# main.net
KiCad netlist of a schematic drawn in Altium Designer
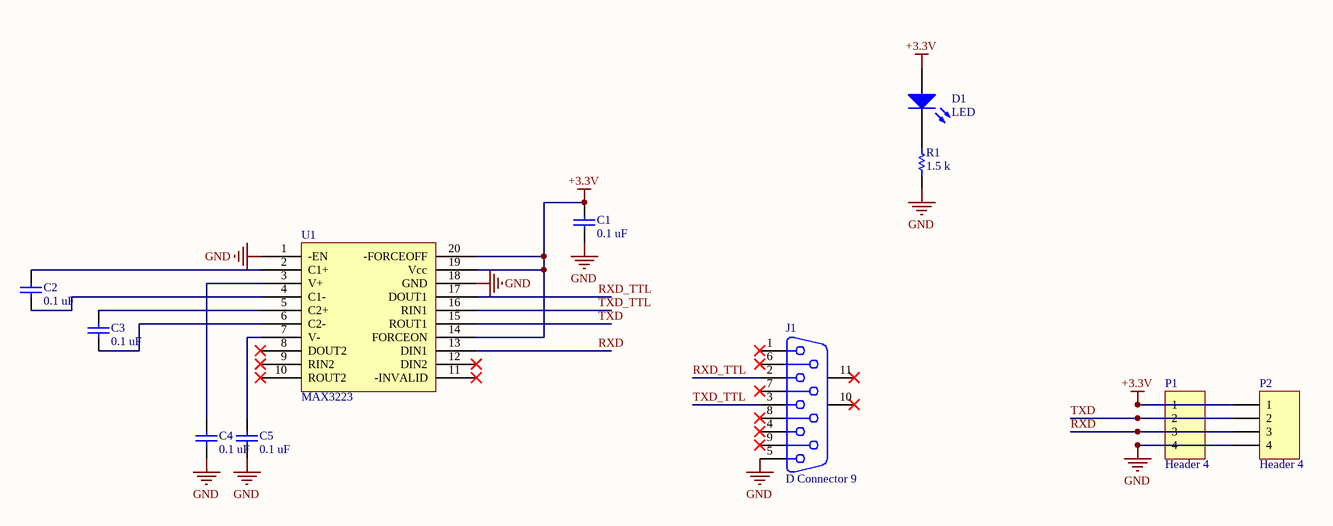
[diagram p0: main.SchDoc]

(export (version "E")
  (design (tool "Eeschema 10.0.6"))
  (components
    (comp (ref "C1")
      (value "0.1 uF")
      (footprint "0603")
      (description "Capacitor")
      (libsource (lib "allspace_schem") (part "Capacitor"))
    )
    (comp (ref "C2")
      (value "0.1 uF")
      (footprint "0603")
      (description "Capacitor")
      (libsource (lib "allspace_schem") (part "Capacitor"))
    )
    (comp (ref "C3")
      (value "0.1 uF")
      (footprint "0603")
      (description "Capacitor")
      (libsource (lib "allspace_schem") (part "Capacitor"))
    )
    (comp (ref "C4")
      (value "0.1 uF")
      (footprint "0603")
      (description "Capacitor")
      (libsource (lib "allspace_schem") (part "Capacitor"))
    )
    (comp (ref "C5")
      (value "0.1 uF")
      (footprint "0603")
      (description "Capacitor")
      (libsource (lib "allspace_schem") (part "Capacitor"))
    )
    (comp (ref "D1")
      (value "LED")
      (footprint "0603")
      (description "Typical INFRARED GaAs LED")
      (libsource (lib "allspace_schem") (part "LED"))
    )
    (comp (ref "J1")
      (value "D Connector 9")
      (footprint "DSUB1.385-2H9")
      (description "Receptacle Assembly, 9 Position, Right Angle")
      (fields (field (name "PUBLISHER") "Altium Limited"))
      (libsource (lib "Miscellaneous Connectors") (part "D Connector 9"))
    )
    (comp (ref "P1")
      (value "Header 4")
      (footprint "HDR1X4")
      (description "Header, 4-Pin")
      (fields (field (name "PUBLISHER") "Altium Limited"))
      (libsource (lib "allspace_schem") (part "Header 4"))
    )
    (comp (ref "P2")
      (value "Header 4")
      (footprint "MICRO-04-R-SMT")
      (description "Header, 4-Pin")
      (fields (field (name "PUBLISHER") "Altium Limited"))
      (libsource (lib "allspace_schem") (part "Header 4"))
    )
    (comp (ref "R1")
      (value "1.5 k")
      (footprint "0603")
      (description "Resistor")
      (libsource (lib "allspace_schem") (part "Resistor"))
    )
    (comp (ref "U1")
      (value "MAX3223")
      (footprint "TSSOP-20")
      (libsource (lib "allspace_schem") (part "MAX3223"))
    )
  )
  (nets
    (net (code "1") (name "+3.3V") (class "Default")
      (node (ref "C1") (pin "2") (pinfunction "2_2") (pintype "passive"))
      (node (ref "D1") (pin "1") (pinfunction "A_1") (pintype "passive"))
      (node (ref "P1") (pin "1") (pinfunction "1_1") (pintype "passive"))
      (node (ref "P2") (pin "1") (pinfunction "1_1") (pintype "passive"))
      (node (ref "U1") (pin "14") (pinfunction "FORCEON_14") (pintype "passive"))
      (node (ref "U1") (pin "19") (pinfunction "Vcc_19") (pintype "passive"))
      (node (ref "U1") (pin "20") (pinfunction "-FORCEOFF_20") (pintype "passive"))
    )
    (net (code "2") (name "/RXD") (class "Default")
      (node (ref "P1") (pin "3") (pinfunction "3_3") (pintype "passive"))
      (node (ref "P2") (pin "3") (pinfunction "3_3") (pintype "passive"))
      (node (ref "U1") (pin "13") (pinfunction "DIN1_13") (pintype "passive"))
    )
    (net (code "3") (name "/RXD_TTL") (class "Default")
      (node (ref "J1") (pin "2") (pinfunction "2_2") (pintype "passive"))
      (node (ref "U1") (pin "17") (pinfunction "DOUT1_17") (pintype "passive"))
    )
    (net (code "4") (name "/TXD") (class "Default")
      (node (ref "P1") (pin "2") (pinfunction "2_2") (pintype "passive"))
      (node (ref "P2") (pin "2") (pinfunction "2_2") (pintype "passive"))
      (node (ref "U1") (pin "15") (pinfunction "ROUT1_15") (pintype "passive"))
    )
    (net (code "5") (name "/TXD_TTL") (class "Default")
      (node (ref "J1") (pin "3") (pinfunction "3_3") (pintype "passive"))
      (node (ref "U1") (pin "16") (pinfunction "RIN1_16") (pintype "passive"))
    )
    (net (code "6") (name "GND") (class "Default")
      (node (ref "C1") (pin "1") (pinfunction "1_1") (pintype "passive"))
      (node (ref "C4") (pin "2") (pinfunction "2_2") (pintype "passive"))
      (node (ref "C5") (pin "1") (pinfunction "1_1") (pintype "passive"))
      (node (ref "J1") (pin "5") (pinfunction "5_5") (pintype "passive"))
      (node (ref "P1") (pin "4") (pinfunction "4_4") (pintype "passive"))
      (node (ref "P2") (pin "4") (pinfunction "4_4") (pintype "passive"))
      (node (ref "R1") (pin "1") (pinfunction "1_1") (pintype "passive"))
      (node (ref "U1") (pin "1") (pinfunction "-EN_1") (pintype "passive"))
      (node (ref "U1") (pin "18") (pinfunction "GND_18") (pintype "passive"))
    )
    (net (code "7") (name "Net-(D1-K)") (class "Default")
      (node (ref "D1") (pin "2") (pinfunction "K_2") (pintype "passive"))
      (node (ref "R1") (pin "2") (pinfunction "2_2") (pintype "passive"))
    )
    (net (code "8") (name "Net-(U1-C1+)") (class "Default")
      (node (ref "C2") (pin "1") (pinfunction "1_1") (pintype "passive"))
      (node (ref "U1") (pin "2") (pinfunction "C1+_2") (pintype "passive"))
    )
    (net (code "9") (name "Net-(U1-C1-)") (class "Default")
      (node (ref "C2") (pin "2") (pinfunction "2_2") (pintype "passive"))
      (node (ref "U1") (pin "4") (pinfunction "C1-_4") (pintype "passive"))
    )
    (net (code "10") (name "Net-(U1-C2+)") (class "Default")
      (node (ref "C3") (pin "2") (pinfunction "2_2") (pintype "passive"))
      (node (ref "U1") (pin "5") (pinfunction "C2+_5") (pintype "passive"))
    )
    (net (code "11") (name "Net-(U1-C2-)") (class "Default")
      (node (ref "C3") (pin "1") (pinfunction "1_1") (pintype "passive"))
      (node (ref "U1") (pin "6") (pinfunction "C2-_6") (pintype "passive"))
    )
    (net (code "12") (name "Net-(U1-V+)") (class "Default")
      (node (ref "C4") (pin "1") (pinfunction "1_1") (pintype "passive"))
      (node (ref "U1") (pin "3") (pinfunction "V+_3") (pintype "passive"))
    )
    (net (code "13") (name "Net-(U1-V-)") (class "Default")
      (node (ref "C5") (pin "2") (pinfunction "2_2") (pintype "passive"))
      (node (ref "U1") (pin "7") (pinfunction "V-_7") (pintype "passive"))
    )
    (net (code "14") (name "unconnected-(J1-MH1-Pad10)") (class "Default")
      (node (ref "J1") (pin "10") (pinfunction "MH1_10") (pintype "passive+no_connect"))
    )
    (net (code "15") (name "unconnected-(J1-MH2-Pad11)") (class "Default")
      (node (ref "J1") (pin "11") (pinfunction "MH2_11") (pintype "passive+no_connect"))
    )
    (net (code "16") (name "unconnected-(J1-Pad1)") (class "Default")
      (node (ref "J1") (pin "1") (pinfunction "1_1") (pintype "passive+no_connect"))
    )
    (net (code "17") (name "unconnected-(J1-Pad4)") (class "Default")
      (node (ref "J1") (pin "4") (pinfunction "4_4") (pintype "passive+no_connect"))
    )
    (net (code "18") (name "unconnected-(J1-Pad6)") (class "Default")
      (node (ref "J1") (pin "6") (pinfunction "6_6") (pintype "passive+no_connect"))
    )
    (net (code "19") (name "unconnected-(J1-Pad7)") (class "Default")
      (node (ref "J1") (pin "7") (pinfunction "7_7") (pintype "passive+no_connect"))
    )
    (net (code "20") (name "unconnected-(J1-Pad8)") (class "Default")
      (node (ref "J1") (pin "8") (pinfunction "8_8") (pintype "passive+no_connect"))
    )
    (net (code "21") (name "unconnected-(J1-Pad9)") (class "Default")
      (node (ref "J1") (pin "9") (pinfunction "9_9") (pintype "passive+no_connect"))
    )
    (net (code "22") (name "unconnected-(U1--INVALID-Pad11)") (class "Default")
      (node (ref "U1") (pin "11") (pinfunction "-INVALID_11") (pintype "passive+no_connect"))
    )
    (net (code "23") (name "unconnected-(U1-DIN2-Pad12)") (class "Default")
      (node (ref "U1") (pin "12") (pinfunction "DIN2_12") (pintype "passive+no_connect"))
    )
    (net (code "24") (name "unconnected-(U1-DOUT2-Pad8)") (class "Default")
      (node (ref "U1") (pin "8") (pinfunction "DOUT2_8") (pintype "passive+no_connect"))
    )
    (net (code "25") (name "unconnected-(U1-RIN2-Pad9)") (class "Default")
      (node (ref "U1") (pin "9") (pinfunction "RIN2_9") (pintype "passive+no_connect"))
    )
    (net (code "26") (name "unconnected-(U1-ROUT2-Pad10)") (class "Default")
      (node (ref "U1") (pin "10") (pinfunction "ROUT2_10") (pintype "passive+no_connect"))
    )
  )
)
